# connectors.net
KiCad netlist of a schematic drawn in Altium Designer
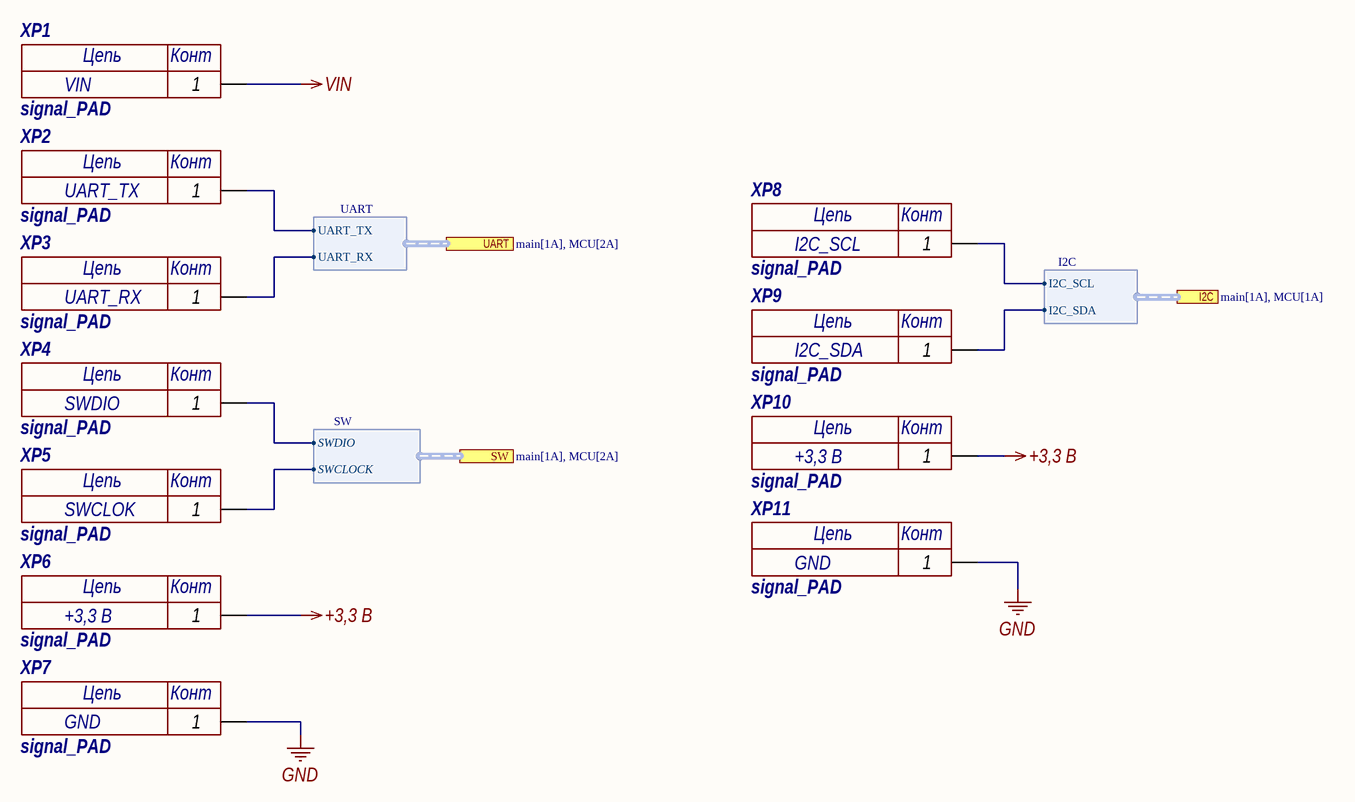
[diagram p0: connectors.SchDoc]

(export (version "E")
  (design (tool "Eeschema 10.0.6"))
  (components
    (comp (ref "XP1")
      (value "signal_PAD")
      (footprint "SS_PAD")
      (description "контактная площадка под пайку тонких проводов")
      (fields (field (name "VALUE1") "VIN"))
      (libsource (lib "Hydrolib") (part "Conn_1pin"))
    )
    (comp (ref "XP2")
      (value "signal_PAD")
      (footprint "SS_PAD")
      (description "контактная площадка под пайку тонких проводов")
      (fields (field (name "VALUE1") "UART_TX"))
      (libsource (lib "Hydrolib") (part "Conn_1pin"))
    )
    (comp (ref "XP3")
      (value "signal_PAD")
      (footprint "SS_PAD")
      (description "контактная площадка под пайку тонких проводов")
      (fields (field (name "VALUE1") "UART_RX"))
      (libsource (lib "Hydrolib") (part "Conn_1pin"))
    )
    (comp (ref "XP4")
      (value "signal_PAD")
      (footprint "SS_PAD")
      (description "контактная площадка под пайку тонких проводов")
      (fields (field (name "VALUE1") "SWDIO"))
      (libsource (lib "Hydrolib") (part "Conn_1pin"))
    )
    (comp (ref "XP5")
      (value "signal_PAD")
      (footprint "SS_PAD")
      (description "контактная площадка под пайку тонких проводов")
      (fields (field (name "VALUE1") "SWCLOK"))
      (libsource (lib "Hydrolib") (part "Conn_1pin"))
    )
    (comp (ref "XP6")
      (value "signal_PAD")
      (footprint "SS_PAD")
      (description "контактная площадка под пайку тонких проводов")
      (fields (field (name "VALUE1") "+3,3 В"))
      (libsource (lib "Hydrolib") (part "Conn_1pin"))
    )
    (comp (ref "XP7")
      (value "signal_PAD")
      (footprint "SS_PAD")
      (description "контактная площадка под пайку тонких проводов")
      (fields (field (name "VALUE1") "GND"))
      (libsource (lib "Hydrolib") (part "Conn_1pin"))
    )
    (comp (ref "XP8")
      (value "signal_PAD")
      (footprint "SS_PAD")
      (description "контактная площадка под пайку тонких проводов")
      (fields (field (name "VALUE1") "I2C_SCL"))
      (libsource (lib "Hydrolib") (part "Conn_1pin"))
    )
    (comp (ref "XP9")
      (value "signal_PAD")
      (footprint "SS_PAD")
      (description "контактная площадка под пайку тонких проводов")
      (fields (field (name "VALUE1") "I2C_SDA"))
      (libsource (lib "Hydrolib") (part "Conn_1pin"))
    )
    (comp (ref "XP10")
      (value "signal_PAD")
      (footprint "SS_PAD")
      (description "контактная площадка под пайку тонких проводов")
      (fields (field (name "VALUE1") "+3,3 В"))
      (libsource (lib "Hydrolib") (part "Conn_1pin"))
    )
    (comp (ref "XP11")
      (value "signal_PAD")
      (footprint "SS_PAD")
      (description "контактная площадка под пайку тонких проводов")
      (fields (field (name "VALUE1") "GND"))
      (libsource (lib "Hydrolib") (part "Conn_1pin"))
    )
  )
  (nets
    (net (code "4") (name "+3,3 В") (class "Default")
      (node (ref "XP10") (pin "1") (pinfunction "1_1") (pintype "passive"))
      (node (ref "XP6") (pin "1") (pinfunction "1_1") (pintype "passive"))
    )
    (net (code "5") (name "/I2C_SCL") (class "Default")
      (node (ref "XP8") (pin "1") (pinfunction "1_1") (pintype "passive"))
    )
    (net (code "6") (name "/I2C_SDA") (class "Default")
      (node (ref "XP9") (pin "1") (pinfunction "1_1") (pintype "passive"))
    )
    (net (code "7") (name "/SWCLOCK") (class "Default")
      (node (ref "XP5") (pin "1") (pinfunction "1_1") (pintype "passive"))
    )
    (net (code "8") (name "/SWDIO") (class "Default")
      (node (ref "XP4") (pin "1") (pinfunction "1_1") (pintype "passive"))
    )
    (net (code "9") (name "/UART_RX") (class "Default")
      (node (ref "XP3") (pin "1") (pinfunction "1_1") (pintype "passive"))
    )
    (net (code "10") (name "/UART_TX") (class "Default")
      (node (ref "XP2") (pin "1") (pinfunction "1_1") (pintype "passive"))
    )
    (net (code "14") (name "GND") (class "Default")
      (node (ref "XP11") (pin "1") (pinfunction "1_1") (pintype "passive"))
      (node (ref "XP7") (pin "1") (pinfunction "1_1") (pintype "passive"))
    )
    (net (code "15") (name "VIN") (class "Default")
      (node (ref "XP1") (pin "1") (pinfunction "1_1") (pintype "passive"))
    )
  )
)
